# 1x9x1_3.net
KiCad netlist of a schematic drawn in Altium Designer
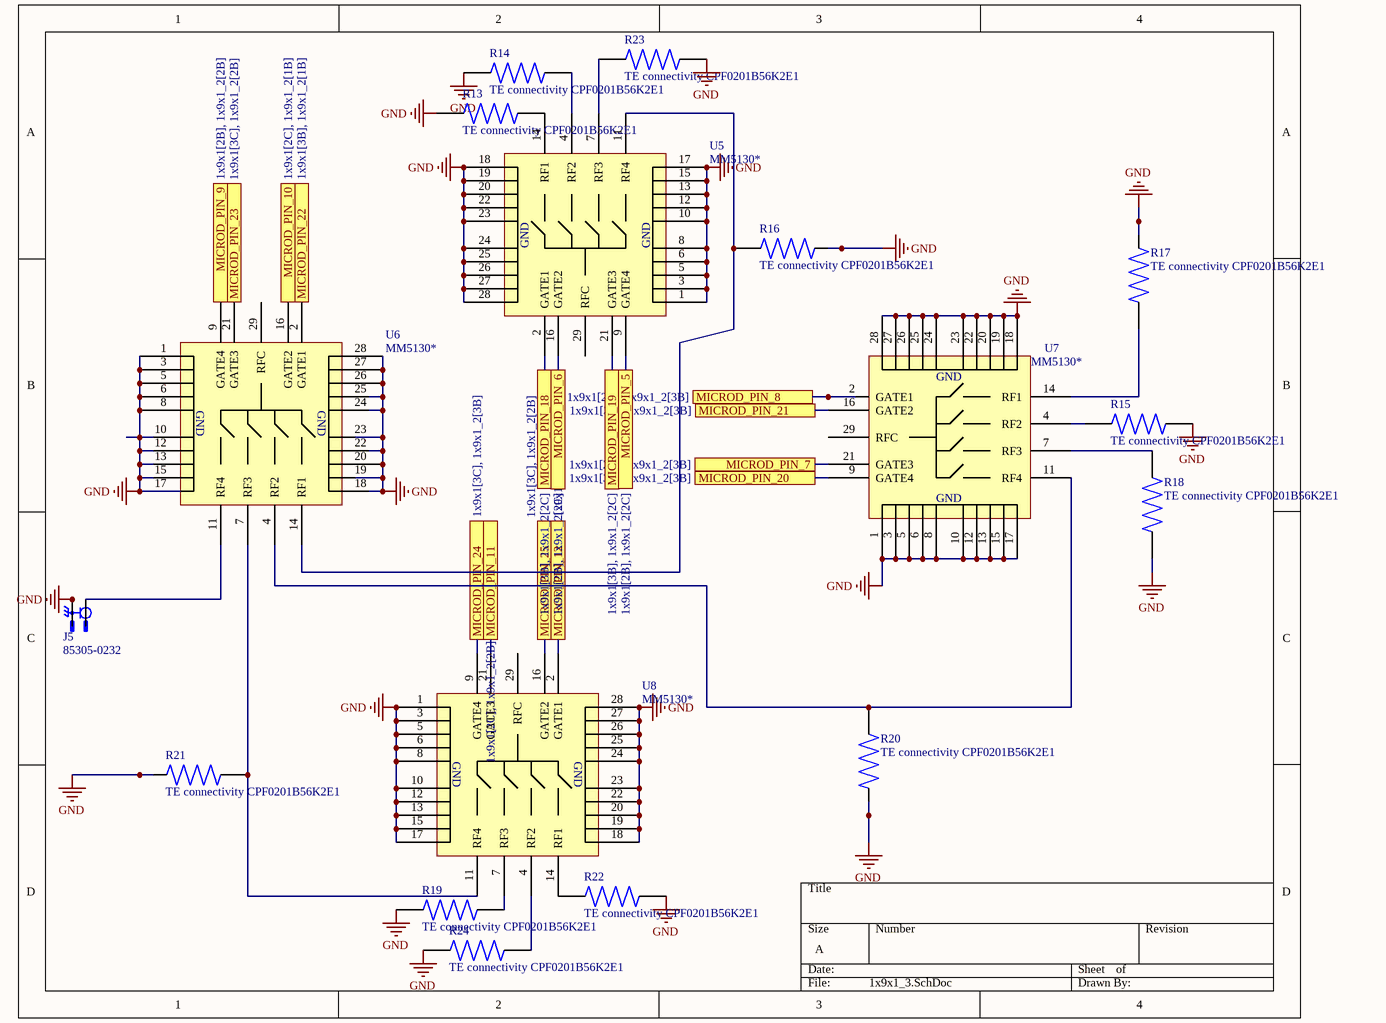
[diagram p0: 1x9x1_3.SchDoc]

(export (version "E")
  (design (tool "Eeschema 10.0.6"))
  (components
    (comp (ref "J5")
      (value "85305-0232")
      (footprint "MOLEX_85305-0232")
      (description "SMP Connector Plug, Male Pin 50Ohm Surface Mount Solder")
      (fields (field (name "MP") "853050232") (field (name "MF") "Molex"))
      (libsource (lib "85305-0232") (part "85305-0232"))
    )
    (comp (ref "R13")
      (value "TE connectivity CPF0201B56K2E1")
      (footprint "0201-resistor")
      (description "CPF 0201 56K2 0.1% 25PPM 1K RL")
      (fields (field (name "MP") "ERJ1GN0R00C") (field (name "MFGR PART NO.") "CPF0201B56K2E1"))
      (libsource (lib "SchlibLafe") (part "TE connectivity CPF0201B56K2E1"))
    )
    (comp (ref "R14")
      (value "TE connectivity CPF0201B56K2E1")
      (footprint "0201-resistor")
      (description "CPF 0201 56K2 0.1% 25PPM 1K RL")
      (fields (field (name "MP") "ERJ1GN0R00C") (field (name "MFGR PART NO.") "CPF0201B56K2E1"))
      (libsource (lib "SchlibLafe") (part "TE connectivity CPF0201B56K2E1"))
    )
    (comp (ref "R15")
      (value "TE connectivity CPF0201B56K2E1")
      (footprint "0201-resistor")
      (description "CPF 0201 56K2 0.1% 25PPM 1K RL")
      (fields (field (name "MP") "ERJ1GN0R00C") (field (name "MFGR PART NO.") "CPF0201B56K2E1"))
      (libsource (lib "SchlibLafe") (part "TE connectivity CPF0201B56K2E1"))
    )
    (comp (ref "R16")
      (value "TE connectivity CPF0201B56K2E1")
      (footprint "0201-resistor")
      (description "CPF 0201 56K2 0.1% 25PPM 1K RL")
      (fields (field (name "MP") "ERJ1GN0R00C") (field (name "MFGR PART NO.") "CPF0201B56K2E1"))
      (libsource (lib "SchlibLafe") (part "TE connectivity CPF0201B56K2E1"))
    )
    (comp (ref "R17")
      (value "TE connectivity CPF0201B56K2E1")
      (footprint "0201-resistor")
      (description "CPF 0201 56K2 0.1% 25PPM 1K RL")
      (fields (field (name "MP") "ERJ1GN0R00C") (field (name "MFGR PART NO.") "CPF0201B56K2E1"))
      (libsource (lib "SchlibLafe") (part "TE connectivity CPF0201B56K2E1"))
    )
    (comp (ref "R18")
      (value "TE connectivity CPF0201B56K2E1")
      (footprint "0201-resistor")
      (description "CPF 0201 56K2 0.1% 25PPM 1K RL")
      (fields (field (name "MP") "ERJ1GN0R00C") (field (name "MFGR PART NO.") "CPF0201B56K2E1"))
      (libsource (lib "SchlibLafe") (part "TE connectivity CPF0201B56K2E1"))
    )
    (comp (ref "R19")
      (value "TE connectivity CPF0201B56K2E1")
      (footprint "0201-resistor")
      (description "CPF 0201 56K2 0.1% 25PPM 1K RL")
      (fields (field (name "MP") "ERJ1GN0R00C") (field (name "MFGR PART NO.") "CPF0201B56K2E1"))
      (libsource (lib "SchlibLafe") (part "TE connectivity CPF0201B56K2E1"))
    )
    (comp (ref "R20")
      (value "TE connectivity CPF0201B56K2E1")
      (footprint "0201-resistor")
      (description "CPF 0201 56K2 0.1% 25PPM 1K RL")
      (fields (field (name "MP") "ERJ1GN0R00C") (field (name "MFGR PART NO.") "CPF0201B56K2E1"))
      (libsource (lib "SchlibLafe") (part "TE connectivity CPF0201B56K2E1"))
    )
    (comp (ref "R21")
      (value "TE connectivity CPF0201B56K2E1")
      (footprint "0201-resistor")
      (description "CPF 0201 56K2 0.1% 25PPM 1K RL")
      (fields (field (name "MP") "ERJ1GN0R00C") (field (name "MFGR PART NO.") "CPF0201B56K2E1"))
      (libsource (lib "SchlibLafe") (part "TE connectivity CPF0201B56K2E1"))
    )
    (comp (ref "R22")
      (value "TE connectivity CPF0201B56K2E1")
      (footprint "0201-resistor")
      (description "CPF 0201 56K2 0.1% 25PPM 1K RL")
      (fields (field (name "MP") "ERJ1GN0R00C") (field (name "MFGR PART NO.") "CPF0201B56K2E1"))
      (libsource (lib "SchlibLafe") (part "TE connectivity CPF0201B56K2E1"))
    )
    (comp (ref "R23")
      (value "TE connectivity CPF0201B56K2E1")
      (footprint "0201-resistor")
      (description "CPF 0201 56K2 0.1% 25PPM 1K RL")
      (fields (field (name "MP") "ERJ1GN0R00C") (field (name "MFGR PART NO.") "CPF0201B56K2E1"))
      (libsource (lib "SchlibLafe") (part "TE connectivity CPF0201B56K2E1"))
    )
    (comp (ref "R24")
      (value "TE connectivity CPF0201B56K2E1")
      (footprint "0201-resistor")
      (description "CPF 0201 56K2 0.1% 25PPM 1K RL")
      (fields (field (name "MP") "ERJ1GN0R00C") (field (name "MFGR PART NO.") "CPF0201B56K2E1"))
      (libsource (lib "SchlibLafe") (part "TE connectivity CPF0201B56K2E1"))
    )
    (comp (ref "U5")
      (value "MM5130*")
      (footprint "MM5130-NORM_PCB_NOFLOOD")
      (description "High power SP4T MEMs switch")
      (libsource (lib "") (part "IC-MM5130_1"))
    )
    (comp (ref "U6")
      (value "MM5130*")
      (footprint "MM5130-NORM_PCB_NOFLOOD")
      (description "High power SP4T MEMs switch")
      (libsource (lib "") (part "IC-MM5130_2"))
    )
    (comp (ref "U7")
      (value "MM5130*")
      (footprint "MM5130-NORM_PCB_NOFLOOD")
      (description "High power SP4T MEMs switch")
      (libsource (lib "MM5130_SCHSYM") (part "IC-MM5130"))
    )
    (comp (ref "U8")
      (value "MM5130*")
      (footprint "MM5130-NORM_PCB_NOFLOOD")
      (description "High power SP4T MEMs switch")
      (libsource (lib "") (part "IC-MM5130_2"))
    )
  )
  (nets
    (net (code "1") (name "/MICROD_PIN_5") (class "Default")
      (node (ref "U5") (pin "9") (pinfunction "GATE4_9") (pintype "passive"))
    )
    (net (code "2") (name "/MICROD_PIN_6") (class "Default")
      (node (ref "U5") (pin "16") (pinfunction "GATE2_16") (pintype "passive"))
    )
    (net (code "3") (name "/MICROD_PIN_7") (class "Default")
      (node (ref "U7") (pin "21") (pinfunction "GATE3_21") (pintype "passive"))
    )
    (net (code "4") (name "/MICROD_PIN_8") (class "Default")
      (node (ref "U7") (pin "2") (pinfunction "GATE1_2") (pintype "passive"))
    )
    (net (code "5") (name "/MICROD_PIN_9") (class "Default")
      (node (ref "U6") (pin "9") (pinfunction "GATE4_9") (pintype "passive"))
    )
    (net (code "6") (name "/MICROD_PIN_10") (class "Default")
      (node (ref "U6") (pin "16") (pinfunction "GATE2_16") (pintype "passive"))
    )
    (net (code "7") (name "/MICROD_PIN_11") (class "Default")
      (node (ref "U8") (pin "21") (pinfunction "GATE3_21") (pintype "passive"))
    )
    (net (code "8") (name "/MICROD_PIN_12") (class "Default")
      (node (ref "U8") (pin "2") (pinfunction "GATE1_2") (pintype "passive"))
    )
    (net (code "9") (name "/MICROD_PIN_18") (class "Default")
      (node (ref "U5") (pin "2") (pinfunction "GATE1_2") (pintype "passive"))
    )
    (net (code "10") (name "/MICROD_PIN_19") (class "Default")
      (node (ref "U5") (pin "21") (pinfunction "GATE3_21") (pintype "passive"))
    )
    (net (code "11") (name "/MICROD_PIN_20") (class "Default")
      (node (ref "U7") (pin "9") (pinfunction "GATE4_9") (pintype "passive"))
    )
    (net (code "12") (name "/MICROD_PIN_21") (class "Default")
      (node (ref "U7") (pin "16") (pinfunction "GATE2_16") (pintype "passive"))
    )
    (net (code "13") (name "/MICROD_PIN_22") (class "Default")
      (node (ref "U6") (pin "2") (pinfunction "GATE1_2") (pintype "passive"))
    )
    (net (code "14") (name "/MICROD_PIN_23") (class "Default")
      (node (ref "U6") (pin "21") (pinfunction "GATE3_21") (pintype "passive"))
    )
    (net (code "15") (name "/MICROD_PIN_24") (class "Default")
      (node (ref "U8") (pin "9") (pinfunction "GATE4_9") (pintype "passive"))
    )
    (net (code "16") (name "/MICROD_PIN_25") (class "Default")
      (node (ref "U8") (pin "16") (pinfunction "GATE2_16") (pintype "passive"))
    )
    (net (code "17") (name "GND") (class "Default")
      (node (ref "J5") (pin "10") (pinfunction "2_10") (pintype "passive"))
      (node (ref "J5") (pin "11") (pinfunction "2_11") (pintype "passive"))
      (node (ref "J5") (pin "12") (pinfunction "2_12") (pintype "passive"))
      (node (ref "J5") (pin "13") (pinfunction "2_13") (pintype "passive"))
      (node (ref "J5") (pin "14") (pinfunction "2_14") (pintype "passive"))
      (node (ref "J5") (pin "15") (pinfunction "2_15") (pintype "passive"))
      (node (ref "J5") (pin "16") (pinfunction "2_16") (pintype "passive"))
      (node (ref "J5") (pin "17") (pinfunction "2_17") (pintype "passive"))
      (node (ref "J5") (pin "18") (pinfunction "2_18") (pintype "passive"))
      (node (ref "J5") (pin "2") (pinfunction "2_2") (pintype "passive"))
      (node (ref "J5") (pin "3") (pinfunction "2_3") (pintype "passive"))
      (node (ref "J5") (pin "4") (pinfunction "2_4") (pintype "passive"))
      (node (ref "J5") (pin "5") (pinfunction "2_5") (pintype "passive"))
      (node (ref "J5") (pin "6") (pinfunction "2_6") (pintype "passive"))
      (node (ref "J5") (pin "7") (pinfunction "2_7") (pintype "passive"))
      (node (ref "J5") (pin "8") (pinfunction "2_8") (pintype "passive"))
      (node (ref "J5") (pin "9") (pinfunction "2_9") (pintype "passive"))
      (node (ref "R13") (pin "1") (pinfunction "1_1") (pintype "passive"))
      (node (ref "R14") (pin "2") (pinfunction "2_2") (pintype "passive"))
      (node (ref "R15") (pin "2") (pinfunction "2_2") (pintype "passive"))
      (node (ref "R16") (pin "1") (pinfunction "1_1") (pintype "passive"))
      (node (ref "R17") (pin "1") (pinfunction "1_1") (pintype "passive"))
      (node (ref "R18") (pin "1") (pinfunction "1_1") (pintype "passive"))
      (node (ref "R19") (pin "1") (pinfunction "1_1") (pintype "passive"))
      (node (ref "R20") (pin "2") (pinfunction "2_2") (pintype "passive"))
      (node (ref "R21") (pin "2") (pinfunction "2_2") (pintype "passive"))
      (node (ref "R22") (pin "1") (pinfunction "1_1") (pintype "passive"))
      (node (ref "R23") (pin "1") (pinfunction "1_1") (pintype "passive"))
      (node (ref "R24") (pin "1") (pinfunction "1_1") (pintype "passive"))
      (node (ref "U5") (pin "1") (pinfunction "GND_1") (pintype "passive"))
      (node (ref "U5") (pin "10") (pinfunction "GND_10") (pintype "passive"))
      (node (ref "U5") (pin "12") (pinfunction "GND_12") (pintype "passive"))
      (node (ref "U5") (pin "13") (pinfunction "GND_13") (pintype "passive"))
      (node (ref "U5") (pin "15") (pinfunction "GND_15") (pintype "passive"))
      (node (ref "U5") (pin "17") (pinfunction "GND_17") (pintype "passive"))
      (node (ref "U5") (pin "18") (pinfunction "GND_18") (pintype "passive"))
      (node (ref "U5") (pin "19") (pinfunction "GND_19") (pintype "passive"))
      (node (ref "U5") (pin "20") (pinfunction "GND_20") (pintype "passive"))
      (node (ref "U5") (pin "22") (pinfunction "GND_22") (pintype "passive"))
      (node (ref "U5") (pin "23") (pinfunction "GND_23") (pintype "passive"))
      (node (ref "U5") (pin "24") (pinfunction "GND_24") (pintype "passive"))
      (node (ref "U5") (pin "25") (pinfunction "GND_25") (pintype "passive"))
      (node (ref "U5") (pin "26") (pinfunction "GND_26") (pintype "passive"))
      (node (ref "U5") (pin "27") (pinfunction "GND_27") (pintype "passive"))
      (node (ref "U5") (pin "28") (pinfunction "GND_28") (pintype "passive"))
      (node (ref "U5") (pin "3") (pinfunction "GND_3") (pintype "passive"))
      (node (ref "U5") (pin "5") (pinfunction "GND_5") (pintype "passive"))
      (node (ref "U5") (pin "6") (pinfunction "GND_6") (pintype "passive"))
      (node (ref "U5") (pin "8") (pinfunction "GND_8") (pintype "passive"))
      (node (ref "U6") (pin "1") (pinfunction "GND_1") (pintype "passive"))
      (node (ref "U6") (pin "10") (pinfunction "GND_10") (pintype "passive"))
      (node (ref "U6") (pin "12") (pinfunction "GND_12") (pintype "passive"))
      (node (ref "U6") (pin "13") (pinfunction "GND_13") (pintype "passive"))
      (node (ref "U6") (pin "15") (pinfunction "GND_15") (pintype "passive"))
      (node (ref "U6") (pin "17") (pinfunction "GND_17") (pintype "passive"))
      (node (ref "U6") (pin "18") (pinfunction "GND_18") (pintype "passive"))
      (node (ref "U6") (pin "19") (pinfunction "GND_19") (pintype "passive"))
      (node (ref "U6") (pin "20") (pinfunction "GND_20") (pintype "passive"))
      (node (ref "U6") (pin "22") (pinfunction "GND_22") (pintype "passive"))
      (node (ref "U6") (pin "23") (pinfunction "GND_23") (pintype "passive"))
      (node (ref "U6") (pin "24") (pinfunction "GND_24") (pintype "passive"))
      (node (ref "U6") (pin "25") (pinfunction "GND_25") (pintype "passive"))
      (node (ref "U6") (pin "26") (pinfunction "GND_26") (pintype "passive"))
      (node (ref "U6") (pin "27") (pinfunction "GND_27") (pintype "passive"))
      (node (ref "U6") (pin "28") (pinfunction "GND_28") (pintype "passive"))
      (node (ref "U6") (pin "3") (pinfunction "GND_3") (pintype "passive"))
      (node (ref "U6") (pin "5") (pinfunction "GND_5") (pintype "passive"))
      (node (ref "U6") (pin "6") (pinfunction "GND_6") (pintype "passive"))
      (node (ref "U6") (pin "8") (pinfunction "GND_8") (pintype "passive"))
      (node (ref "U7") (pin "1") (pinfunction "GND_1") (pintype "passive"))
      (node (ref "U7") (pin "10") (pinfunction "GND_10") (pintype "passive"))
      (node (ref "U7") (pin "12") (pinfunction "GND_12") (pintype "passive"))
      (node (ref "U7") (pin "13") (pinfunction "GND_13") (pintype "passive"))
      (node (ref "U7") (pin "15") (pinfunction "GND_15") (pintype "passive"))
      (node (ref "U7") (pin "17") (pinfunction "GND_17") (pintype "passive"))
      (node (ref "U7") (pin "18") (pinfunction "GND_18") (pintype "passive"))
      (node (ref "U7") (pin "19") (pinfunction "GND_19") (pintype "passive"))
      (node (ref "U7") (pin "20") (pinfunction "GND_20") (pintype "passive"))
      (node (ref "U7") (pin "22") (pinfunction "GND_22") (pintype "passive"))
      (node (ref "U7") (pin "23") (pinfunction "GND_23") (pintype "passive"))
      (node (ref "U7") (pin "24") (pinfunction "GND_24") (pintype "passive"))
      (node (ref "U7") (pin "25") (pinfunction "GND_25") (pintype "passive"))
      (node (ref "U7") (pin "26") (pinfunction "GND_26") (pintype "passive"))
      (node (ref "U7") (pin "27") (pinfunction "GND_27") (pintype "passive"))
      (node (ref "U7") (pin "28") (pinfunction "GND_28") (pintype "passive"))
      (node (ref "U7") (pin "3") (pinfunction "GND_3") (pintype "passive"))
      (node (ref "U7") (pin "5") (pinfunction "GND_5") (pintype "passive"))
      (node (ref "U7") (pin "6") (pinfunction "GND_6") (pintype "passive"))
      (node (ref "U7") (pin "8") (pinfunction "GND_8") (pintype "passive"))
      (node (ref "U8") (pin "1") (pinfunction "GND_1") (pintype "passive"))
      (node (ref "U8") (pin "10") (pinfunction "GND_10") (pintype "passive"))
      (node (ref "U8") (pin "12") (pinfunction "GND_12") (pintype "passive"))
      (node (ref "U8") (pin "13") (pinfunction "GND_13") (pintype "passive"))
      (node (ref "U8") (pin "15") (pinfunction "GND_15") (pintype "passive"))
      (node (ref "U8") (pin "17") (pinfunction "GND_17") (pintype "passive"))
      (node (ref "U8") (pin "18") (pinfunction "GND_18") (pintype "passive"))
      (node (ref "U8") (pin "19") (pinfunction "GND_19") (pintype "passive"))
      (node (ref "U8") (pin "20") (pinfunction "GND_20") (pintype "passive"))
      (node (ref "U8") (pin "22") (pinfunction "GND_22") (pintype "passive"))
      (node (ref "U8") (pin "23") (pinfunction "GND_23") (pintype "passive"))
      (node (ref "U8") (pin "24") (pinfunction "GND_24") (pintype "passive"))
      (node (ref "U8") (pin "25") (pinfunction "GND_25") (pintype "passive"))
      (node (ref "U8") (pin "26") (pinfunction "GND_26") (pintype "passive"))
      (node (ref "U8") (pin "27") (pinfunction "GND_27") (pintype "passive"))
      (node (ref "U8") (pin "28") (pinfunction "GND_28") (pintype "passive"))
      (node (ref "U8") (pin "3") (pinfunction "GND_3") (pintype "passive"))
      (node (ref "U8") (pin "5") (pinfunction "GND_5") (pintype "passive"))
      (node (ref "U8") (pin "6") (pinfunction "GND_6") (pintype "passive"))
      (node (ref "U8") (pin "8") (pinfunction "GND_8") (pintype "passive"))
    )
    (net (code "18") (name "Net-(U5-RF1)") (class "Default")
      (node (ref "R13") (pin "2") (pinfunction "2_2") (pintype "passive"))
      (node (ref "U5") (pin "14") (pinfunction "RF1_14") (pintype "passive"))
    )
    (net (code "19") (name "Net-(U5-RF2)") (class "Default")
      (node (ref "R14") (pin "1") (pinfunction "1_1") (pintype "passive"))
      (node (ref "U5") (pin "4") (pinfunction "RF2_4") (pintype "passive"))
    )
    (net (code "20") (name "Net-(U5-RF3)") (class "Default")
      (node (ref "R23") (pin "2") (pinfunction "2_2") (pintype "passive"))
      (node (ref "U5") (pin "7") (pinfunction "RF3_7") (pintype "passive"))
    )
    (net (code "21") (name "Net-(U5-RF4)") (class "Default")
      (node (ref "R16") (pin "2") (pinfunction "2_2") (pintype "passive"))
      (node (ref "U5") (pin "11") (pinfunction "RF4_11") (pintype "passive"))
      (node (ref "U6") (pin "14") (pinfunction "RF1_14") (pintype "passive"))
    )
    (net (code "22") (name "Net-(U6-RF2)") (class "Default")
      (node (ref "R20") (pin "1") (pinfunction "1_1") (pintype "passive"))
      (node (ref "U6") (pin "4") (pinfunction "RF2_4") (pintype "passive"))
      (node (ref "U7") (pin "11") (pinfunction "RF4_11") (pintype "passive"))
    )
    (net (code "23") (name "Net-(U6-RF3)") (class "Default")
      (node (ref "R21") (pin "1") (pinfunction "1_1") (pintype "passive"))
      (node (ref "U6") (pin "7") (pinfunction "RF3_7") (pintype "passive"))
      (node (ref "U8") (pin "11") (pinfunction "RF4_11") (pintype "passive"))
    )
    (net (code "24") (name "Net-(U6-RF4)") (class "Default")
      (node (ref "J5") (pin "1") (pinfunction "1_1") (pintype "passive"))
      (node (ref "U6") (pin "11") (pinfunction "RF4_11") (pintype "passive"))
    )
    (net (code "25") (name "Net-(U7-RF1)") (class "Default")
      (node (ref "R17") (pin "2") (pinfunction "2_2") (pintype "passive"))
      (node (ref "U7") (pin "14") (pinfunction "RF1_14") (pintype "passive"))
    )
    (net (code "26") (name "Net-(U7-RF2)") (class "Default")
      (node (ref "R15") (pin "1") (pinfunction "1_1") (pintype "passive"))
      (node (ref "U7") (pin "4") (pinfunction "RF2_4") (pintype "passive"))
    )
    (net (code "27") (name "Net-(U7-RF3)") (class "Default")
      (node (ref "R18") (pin "2") (pinfunction "2_2") (pintype "passive"))
      (node (ref "U7") (pin "7") (pinfunction "RF3_7") (pintype "passive"))
    )
    (net (code "28") (name "Net-(U8-RF1)") (class "Default")
      (node (ref "R22") (pin "2") (pinfunction "2_2") (pintype "passive"))
      (node (ref "U8") (pin "14") (pinfunction "RF1_14") (pintype "passive"))
    )
    (net (code "29") (name "Net-(U8-RF2)") (class "Default")
      (node (ref "R24") (pin "2") (pinfunction "2_2") (pintype "passive"))
      (node (ref "U8") (pin "4") (pinfunction "RF2_4") (pintype "passive"))
    )
    (net (code "30") (name "Net-(U8-RF3)") (class "Default")
      (node (ref "R19") (pin "2") (pinfunction "2_2") (pintype "passive"))
      (node (ref "U8") (pin "7") (pinfunction "RF3_7") (pintype "passive"))
    )
    (net (code "31") (name "unconnected-(U5-RFC-Pad29)") (class "Default")
      (node (ref "U5") (pin "29") (pinfunction "RFC_29") (pintype "passive"))
    )
    (net (code "32") (name "unconnected-(U6-RFC-Pad29)") (class "Default")
      (node (ref "U6") (pin "29") (pinfunction "RFC_29") (pintype "passive"))
    )
    (net (code "33") (name "unconnected-(U7-RFC-Pad29)") (class "Default")
      (node (ref "U7") (pin "29") (pinfunction "RFC_29") (pintype "passive"))
    )
    (net (code "34") (name "unconnected-(U8-RFC-Pad29)") (class "Default")
      (node (ref "U8") (pin "29") (pinfunction "RFC_29") (pintype "passive"))
    )
  )
)
